# recepteur_ir.net
KiCad netlist of a schematic drawn in EAGLE
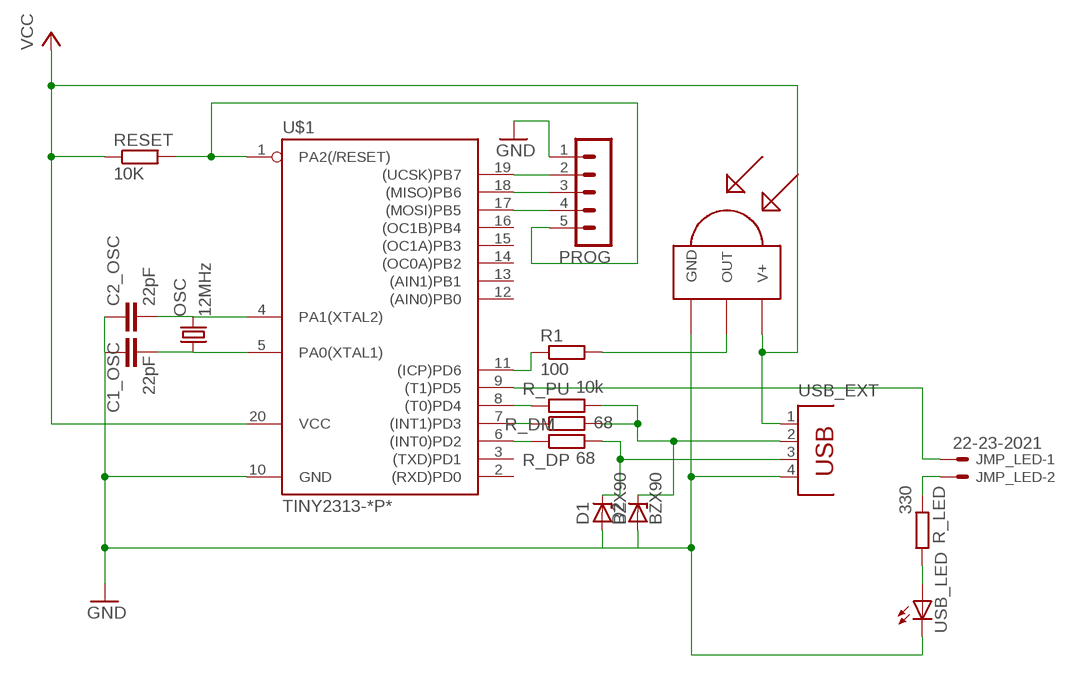
[diagram p0: schematic, sheet 1]

(export (version "E")
  (design (tool "Eeschema 10.0.6"))
  (components
    (comp (ref "C1_OSC")
      (value "22pF")
      (footprint "eagle-import:C025-040X050")
      (libsource (lib "eagle-import") (part "C-EU025-040X050"))
    )
    (comp (ref "C2_OSC")
      (value "22pF")
      (footprint "eagle-import:C025-040X050")
      (libsource (lib "eagle-import") (part "C-EU025-040X050"))
    )
    (comp (ref "D1")
      (value "BZX90")
      (footprint "eagle-import:DO34Z7")
      (libsource (lib "eagle-import") (part "BZX90"))
    )
    (comp (ref "D2")
      (value "BZX90")
      (footprint "eagle-import:DO34Z7")
      (libsource (lib "eagle-import") (part "BZX90"))
    )
    (comp (ref "JMP_LED")
      (value "22-23-2021")
      (footprint "eagle-import:22-23-2021")
      (fields (field (name "MF") "MOLEX"))
      (libsource (lib "eagle-import") (part "22-23-2021"))
    )
    (comp (ref "OSC")
      (value "12MHz")
      (footprint "eagle-import:HC49_S")
      (libsource (lib "eagle-import") (part "CRYSTALHC49S"))
    )
    (comp (ref "PROG")
      (value "MA05-1")
      (footprint "eagle-import:MA05-1")
      (libsource (lib "eagle-import") (part "MA05-1"))
    )
    (comp (ref "R1")
      (value "100")
      (footprint "eagle-import:0204_7")
      (libsource (lib "eagle-import") (part "R-EU_0204/7"))
    )
    (comp (ref "RESET")
      (value "10K")
      (footprint "eagle-import:0204_7")
      (libsource (lib "eagle-import") (part "R-EU_0204/7"))
    )
    (comp (ref "R_DM")
      (value "68")
      (footprint "eagle-import:0204_7")
      (libsource (lib "eagle-import") (part "R-EU_0204/7"))
    )
    (comp (ref "R_DP")
      (value "68")
      (footprint "eagle-import:0204_7")
      (libsource (lib "eagle-import") (part "R-EU_0204/7"))
    )
    (comp (ref "R_LED")
      (value "330")
      (footprint "eagle-import:0204_7")
      (libsource (lib "eagle-import") (part "R-EU_0204/7"))
    )
    (comp (ref "R_PU")
      (value "10k")
      (footprint "eagle-import:0204_7")
      (libsource (lib "eagle-import") (part "R-EU_0204/7"))
    )
    (comp (ref "U$1")
      (value "TINY2313-*P*")
      (footprint "eagle-import:DIL20")
      (libsource (lib "eagle-import") (part "TINY2313-P"))
    )
    (comp (ref "U$2")
      (value "TSOP2238")
      (footprint "eagle-import:TSOP2XXX")
      (libsource (lib "eagle-import") (part "TSOP2238"))
    )
    (comp (ref "USB_EXT")
      (value "PN61729")
      (footprint "eagle-import:PN61729")
      (libsource (lib "eagle-import") (part "PN61729"))
    )
    (comp (ref "USB_LED")
      (value "LED3MM")
      (footprint "eagle-import:LED3MM")
      (libsource (lib "eagle-import") (part "LED3MM"))
    )
  )
  (nets
    (net (code "1") (name "GND") (class "Default")
      (node (ref "C1_OSC") (pin "1") (pinfunction "1_1") (pintype "passive"))
      (node (ref "C2_OSC") (pin "1") (pinfunction "1_1") (pintype "passive"))
      (node (ref "D1") (pin "A") (pinfunction "A_A") (pintype "passive"))
      (node (ref "D2") (pin "A") (pinfunction "A_A") (pintype "passive"))
      (node (ref "PROG") (pin "1") (pinfunction "1_1") (pintype "passive"))
      (node (ref "U$1") (pin "10") (pinfunction "GND_10") (pintype "power_in"))
      (node (ref "U$2") (pin "GND") (pinfunction "GND_GND") (pintype "bidirectional"))
      (node (ref "USB_EXT") (pin "4") (pinfunction "4_4") (pintype "passive"))
      (node (ref "USB_LED") (pin "K") (pinfunction "C_K") (pintype "passive"))
    )
    (net (code "2") (name "Net-(D1-PadC)") (class "Default")
      (node (ref "D1") (pin "C") (pinfunction "C_C") (pintype "passive"))
      (node (ref "R_DP") (pin "2") (pinfunction "2_2") (pintype "passive"))
      (node (ref "USB_EXT") (pin "3") (pinfunction "3_3") (pintype "passive"))
    )
    (net (code "3") (name "Net-(D2-PadC)") (class "Default")
      (node (ref "D2") (pin "C") (pinfunction "C_C") (pintype "passive"))
      (node (ref "R_DM") (pin "2") (pinfunction "2_2") (pintype "passive"))
      (node (ref "R_PU") (pin "2") (pinfunction "2_2") (pintype "passive"))
      (node (ref "USB_EXT") (pin "2") (pinfunction "2_2") (pintype "passive"))
    )
    (net (code "4") (name "Net-(JMP_LEDA-S)") (class "Default")
      (node (ref "JMP_LED") (pin "1") (pinfunction "S_1") (pintype "passive"))
      (node (ref "U$1") (pin "9") (pinfunction "(T1)PD5_9") (pintype "bidirectional"))
    )
    (net (code "5") (name "Net-(JMP_LEDB-S)") (class "Default")
      (node (ref "JMP_LED") (pin "2") (pinfunction "S_2") (pintype "passive"))
      (node (ref "R_LED") (pin "1") (pinfunction "1_1") (pintype "passive"))
    )
    (net (code "6") (name "Net-(R1-Pad2)") (class "Default")
      (node (ref "R1") (pin "2") (pinfunction "2_2") (pintype "passive"))
      (node (ref "U$2") (pin "OUT") (pinfunction "OUT_OUT") (pintype "bidirectional"))
    )
    (net (code "7") (name "Net-(R_LED-Pad2)") (class "Default")
      (node (ref "R_LED") (pin "2") (pinfunction "2_2") (pintype "passive"))
      (node (ref "USB_LED") (pin "A") (pinfunction "A_A") (pintype "passive"))
    )
    (net (code "8") (name "Net-(U$1-(ICP)PD6)") (class "Default")
      (node (ref "R1") (pin "1") (pinfunction "1_1") (pintype "passive"))
      (node (ref "U$1") (pin "11") (pinfunction "(ICP)PD6_11") (pintype "bidirectional"))
    )
    (net (code "9") (name "Net-(U$1-(INT0)PD2)") (class "Default")
      (node (ref "R_DP") (pin "1") (pinfunction "1_1") (pintype "passive"))
      (node (ref "U$1") (pin "6") (pinfunction "(INT0)PD2_6") (pintype "bidirectional"))
    )
    (net (code "10") (name "Net-(U$1-(INT1)PD3)") (class "Default")
      (node (ref "R_DM") (pin "1") (pinfunction "1_1") (pintype "passive"))
      (node (ref "U$1") (pin "7") (pinfunction "(INT1)PD3_7") (pintype "bidirectional"))
    )
    (net (code "11") (name "Net-(U$1-(MISO)PB6)") (class "Default")
      (node (ref "PROG") (pin "3") (pinfunction "3_3") (pintype "passive"))
      (node (ref "U$1") (pin "18") (pinfunction "(MISO)PB6_18") (pintype "bidirectional"))
    )
    (net (code "12") (name "Net-(U$1-(MOSI)PB5)") (class "Default")
      (node (ref "PROG") (pin "4") (pinfunction "4_4") (pintype "passive"))
      (node (ref "U$1") (pin "17") (pinfunction "(MOSI)PB5_17") (pintype "bidirectional"))
    )
    (net (code "13") (name "Net-(U$1-(T0)PD4)") (class "Default")
      (node (ref "R_PU") (pin "1") (pinfunction "1_1") (pintype "passive"))
      (node (ref "U$1") (pin "8") (pinfunction "(T0)PD4_8") (pintype "bidirectional"))
    )
    (net (code "14") (name "Net-(U$1-(UCSK)PB7)") (class "Default")
      (node (ref "PROG") (pin "2") (pinfunction "2_2") (pintype "passive"))
      (node (ref "U$1") (pin "19") (pinfunction "(UCSK)PB7_19") (pintype "bidirectional"))
    )
    (net (code "15") (name "Net-(U$1-PA0(XTAL1))") (class "Default")
      (node (ref "C1_OSC") (pin "2") (pinfunction "2_2") (pintype "passive"))
      (node (ref "OSC") (pin "1") (pinfunction "1_1") (pintype "passive"))
      (node (ref "U$1") (pin "5") (pinfunction "PA0(XTAL1)_5") (pintype "bidirectional"))
    )
    (net (code "16") (name "Net-(U$1-PA1(XTAL2))") (class "Default")
      (node (ref "C2_OSC") (pin "2") (pinfunction "2_2") (pintype "passive"))
      (node (ref "OSC") (pin "2") (pinfunction "2_2") (pintype "passive"))
      (node (ref "U$1") (pin "4") (pinfunction "PA1(XTAL2)_4") (pintype "bidirectional"))
    )
    (net (code "17") (name "Net-(U$1-PA2({slash}RESET))") (class "Default")
      (node (ref "PROG") (pin "5") (pinfunction "5_5") (pintype "passive"))
      (node (ref "RESET") (pin "2") (pinfunction "2_2") (pintype "passive"))
      (node (ref "U$1") (pin "1") (pinfunction "PA2(/RESET)_1") (pintype "input"))
    )
    (net (code "18") (name "VCC") (class "Default")
      (node (ref "RESET") (pin "1") (pinfunction "1_1") (pintype "passive"))
      (node (ref "U$1") (pin "20") (pinfunction "VCC_20") (pintype "power_in"))
      (node (ref "U$2") (pin "VCC") (pinfunction "V+_VCC") (pintype "bidirectional"))
      (node (ref "USB_EXT") (pin "1") (pinfunction "1_1") (pintype "passive"))
    )
    (net (code "19") (name "unconnected-(U$1-(AIN0)PB0-Pad12)") (class "Default")
      (node (ref "U$1") (pin "12") (pinfunction "(AIN0)PB0_12") (pintype "bidirectional"))
    )
    (net (code "20") (name "unconnected-(U$1-(AIN1)PB1-Pad13)") (class "Default")
      (node (ref "U$1") (pin "13") (pinfunction "(AIN1)PB1_13") (pintype "bidirectional"))
    )
    (net (code "21") (name "unconnected-(U$1-(OC0A)PB2-Pad14)") (class "Default")
      (node (ref "U$1") (pin "14") (pinfunction "(OC0A)PB2_14") (pintype "bidirectional"))
    )
    (net (code "22") (name "unconnected-(U$1-(OC1A)PB3-Pad15)") (class "Default")
      (node (ref "U$1") (pin "15") (pinfunction "(OC1A)PB3_15") (pintype "bidirectional"))
    )
    (net (code "23") (name "unconnected-(U$1-(OC1B)PB4-Pad16)") (class "Default")
      (node (ref "U$1") (pin "16") (pinfunction "(OC1B)PB4_16") (pintype "bidirectional"))
    )
    (net (code "24") (name "unconnected-(U$1-(RXD)PD0-Pad2)") (class "Default")
      (node (ref "U$1") (pin "2") (pinfunction "(RXD)PD0_2") (pintype "bidirectional"))
    )
    (net (code "25") (name "unconnected-(U$1-(TXD)PD1-Pad3)") (class "Default")
      (node (ref "U$1") (pin "3") (pinfunction "(TXD)PD1_3") (pintype "bidirectional"))
    )
  )
)
